# USB.net
KiCad netlist of a schematic drawn in Altium Designer
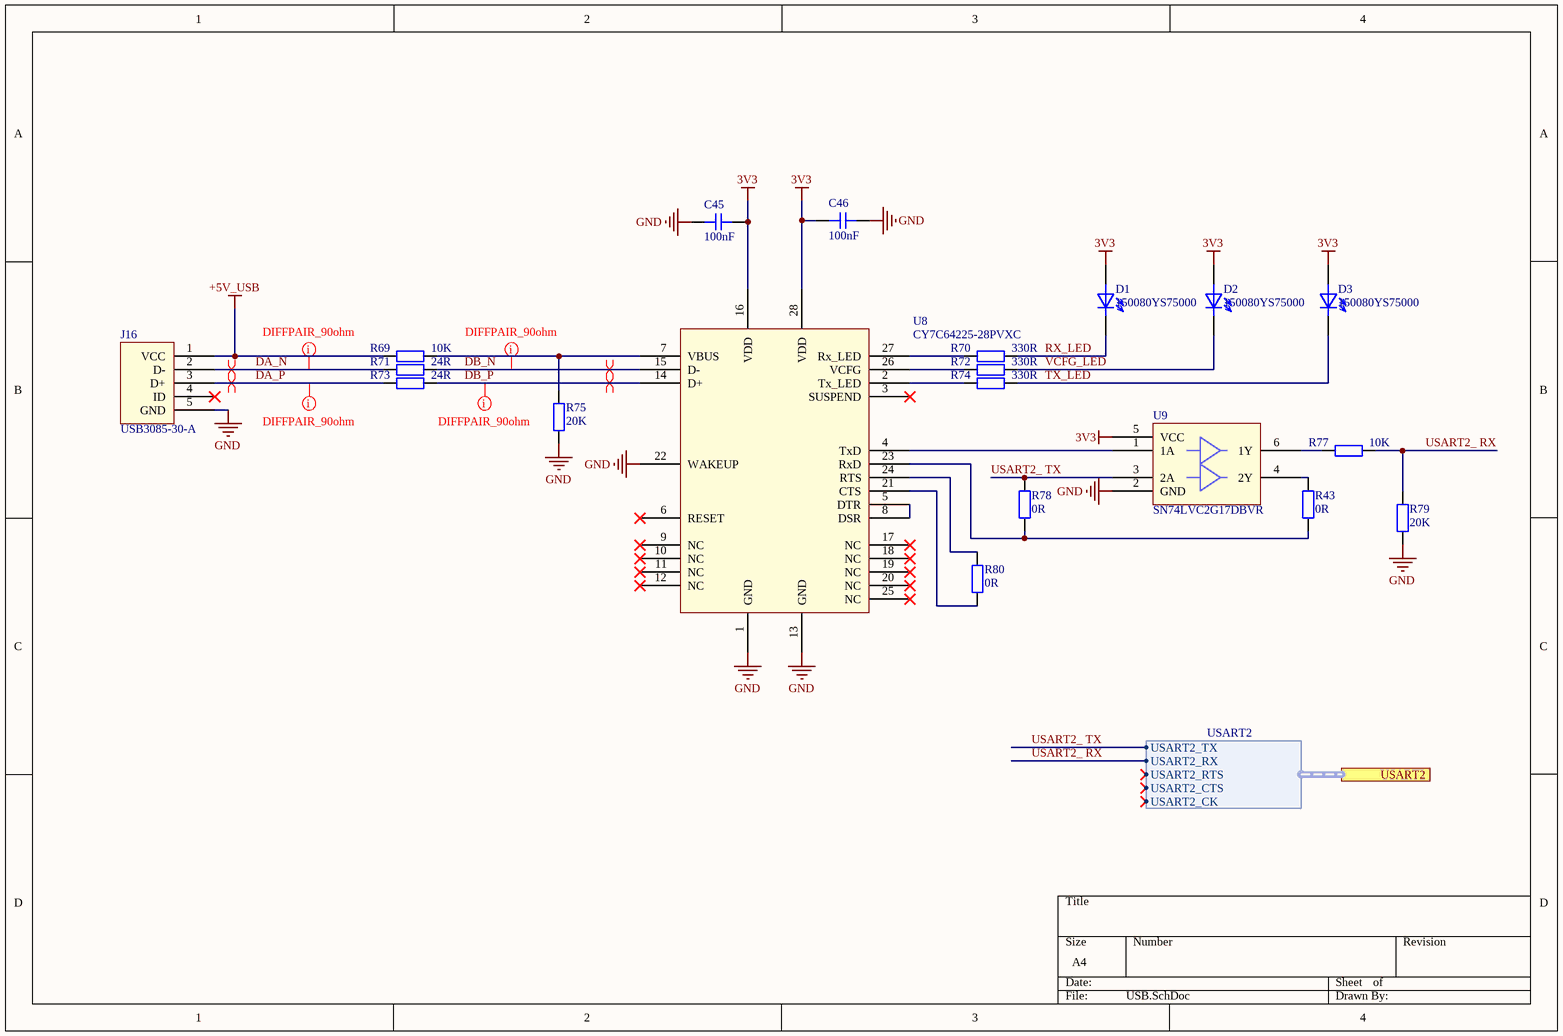
[diagram p0: USB.SchDoc]

(export (version "E")
  (design (tool "Eeschema 10.0.6"))
  (components
    (comp (ref "C45")
      (value "100nF")
      (footprint "Capacitor-0603")
      (fields (field (name "Comment") "C-100nF-0603"))
      (libsource (lib "Components") (part "C-100nF-0603"))
    )
    (comp (ref "C46")
      (value "100nF")
      (footprint "Capacitor-0603")
      (fields (field (name "Comment") "C-100nF-0603"))
      (libsource (lib "Components") (part "C-100nF-0603"))
    )
    (comp (ref "D1")
      (value "150080YS75000")
      (footprint "150080YS75000")
      (libsource (lib "Components") (part "150080YS75000"))
    )
    (comp (ref "D2")
      (value "150080YS75000")
      (footprint "150080YS75000")
      (libsource (lib "Components") (part "150080YS75000"))
    )
    (comp (ref "D3")
      (value "150080YS75000")
      (footprint "150080YS75000")
      (libsource (lib "Components") (part "150080YS75000"))
    )
    (comp (ref "J16")
      (value "USB3085-30-A")
      (footprint "USB3085-30-A")
      (libsource (lib "Components") (part "USB3085-30-A"))
    )
    (comp (ref "R43")
      (value "0R")
      (footprint "Resistor-0603")
      (fields (field (name "Comment") "R-0R-0603"))
      (libsource (lib "Components") (part "R-0R-0603"))
    )
    (comp (ref "R69")
      (value "10K")
      (footprint "Resistor-0603")
      (fields (field (name "Comment") "R-10K-0603"))
      (libsource (lib "Components") (part "R-10K-0603"))
    )
    (comp (ref "R70")
      (value "330R")
      (footprint "Resistor-0603")
      (fields (field (name "Comment") "R-330R-0603"))
      (libsource (lib "Components") (part "R-330R-0603"))
    )
    (comp (ref "R71")
      (value "24R")
      (footprint "Resistor-0603")
      (fields (field (name "Comment") "R-24R-0603"))
      (libsource (lib "Components") (part "R-24R-0603"))
    )
    (comp (ref "R72")
      (value "330R")
      (footprint "Resistor-0603")
      (fields (field (name "Comment") "R-330R-0603"))
      (libsource (lib "Components") (part "R-330R-0603"))
    )
    (comp (ref "R73")
      (value "24R")
      (footprint "Resistor-0603")
      (fields (field (name "Comment") "R-24R-0603"))
      (libsource (lib "Components") (part "R-24R-0603"))
    )
    (comp (ref "R74")
      (value "330R")
      (footprint "Resistor-0603")
      (fields (field (name "Comment") "R-330R-0603"))
      (libsource (lib "Components") (part "R-330R-0603"))
    )
    (comp (ref "R75")
      (value "20K")
      (footprint "Resistor-0603")
      (fields (field (name "Comment") "R-20K-0603"))
      (libsource (lib "Components") (part "R-20K-0603"))
    )
    (comp (ref "R77")
      (value "10K")
      (footprint "Resistor-0603")
      (fields (field (name "Comment") "R-10K-0603"))
      (libsource (lib "Components") (part "R-10K-0603"))
    )
    (comp (ref "R78")
      (value "0R")
      (footprint "Resistor-0603")
      (fields (field (name "Comment") "R-0R-0603"))
      (libsource (lib "Components") (part "R-0R-0603"))
    )
    (comp (ref "R79")
      (value "20K")
      (footprint "Resistor-0603")
      (fields (field (name "Comment") "R-20K-0603"))
      (libsource (lib "Components") (part "R-20K-0603"))
    )
    (comp (ref "R80")
      (value "0R")
      (footprint "Resistor-0603")
      (fields (field (name "Comment") "R-0R-0603"))
      (libsource (lib "Components") (part "R-0R-0603"))
    )
    (comp (ref "U8")
      (value "CY7C64225-28PVXC")
      (footprint "CY7C64225-28PVXC")
      (libsource (lib "Components") (part "CY7C64225-28PVXC"))
    )
    (comp (ref "U9")
      (value "SN74LVC2G17DBVR")
      (footprint "SN74LVC2G17DBVR")
      (libsource (lib "Components") (part "SN74LVC2G17DBVR"))
    )
  )
  (nets
    (net (code "2") (name "+5V_USB") (class "Default")
      (node (ref "J16") (pin "1") (pinfunction "VCC_1") (pintype "passive"))
      (node (ref "R69") (pin "1") (pinfunction "1_1") (pintype "passive"))
    )
    (net (code "3") (name "/DA_N") (class "Default")
      (node (ref "J16") (pin "2") (pinfunction "D-_2") (pintype "passive"))
      (node (ref "R71") (pin "1") (pinfunction "1_1") (pintype "passive"))
    )
    (net (code "4") (name "/DA_P") (class "Default")
      (node (ref "J16") (pin "3") (pinfunction "D+_3") (pintype "passive"))
      (node (ref "R73") (pin "1") (pinfunction "1_1") (pintype "passive"))
    )
    (net (code "5") (name "/DB_N") (class "Default")
      (node (ref "R71") (pin "2") (pinfunction "2_2") (pintype "passive"))
      (node (ref "U8") (pin "15") (pinfunction "D-_15") (pintype "passive"))
    )
    (net (code "6") (name "/DB_P") (class "Default")
      (node (ref "R73") (pin "2") (pinfunction "2_2") (pintype "passive"))
      (node (ref "U8") (pin "14") (pinfunction "D+_14") (pintype "passive"))
    )
    (net (code "7") (name "/RX_LED") (class "Default")
      (node (ref "D1") (pin "1") (pinfunction "1_1") (pintype "passive"))
      (node (ref "R70") (pin "2") (pinfunction "2_2") (pintype "passive"))
    )
    (net (code "8") (name "/TX_LED") (class "Default")
      (node (ref "D3") (pin "1") (pinfunction "1_1") (pintype "passive"))
      (node (ref "R74") (pin "2") (pinfunction "2_2") (pintype "passive"))
    )
    (net (code "9") (name "/USART2_ RX") (class "Default")
      (node (ref "R77") (pin "2") (pinfunction "2_2") (pintype "passive"))
      (node (ref "R79") (pin "2") (pinfunction "2_2") (pintype "passive"))
    )
    (net (code "10") (name "/USART2_ TX") (class "Default")
      (node (ref "R78") (pin "2") (pinfunction "2_2") (pintype "passive"))
      (node (ref "U9") (pin "3") (pinfunction "2A_3") (pintype "passive"))
    )
    (net (code "11") (name "/VCFG_LED") (class "Default")
      (node (ref "D2") (pin "1") (pinfunction "1_1") (pintype "passive"))
      (node (ref "R72") (pin "2") (pinfunction "2_2") (pintype "passive"))
    )
    (net (code "13") (name "3V3") (class "Default")
      (node (ref "C45") (pin "1") (pinfunction "1_1") (pintype "passive"))
      (node (ref "C46") (pin "1") (pinfunction "1_1") (pintype "passive"))
      (node (ref "D1") (pin "2") (pinfunction "2_2") (pintype "passive"))
      (node (ref "D2") (pin "2") (pinfunction "2_2") (pintype "passive"))
      (node (ref "D3") (pin "2") (pinfunction "2_2") (pintype "passive"))
      (node (ref "U8") (pin "16") (pinfunction "VDD_16") (pintype "passive"))
      (node (ref "U8") (pin "28") (pinfunction "VDD_28") (pintype "passive"))
      (node (ref "U9") (pin "5") (pinfunction "VCC_5") (pintype "passive"))
    )
    (net (code "14") (name "GND") (class "Default")
      (node (ref "C45") (pin "2") (pinfunction "2_2") (pintype "passive"))
      (node (ref "C46") (pin "2") (pinfunction "2_2") (pintype "passive"))
      (node (ref "J16") (pin "5") (pinfunction "GND_5") (pintype "passive"))
      (node (ref "R75") (pin "1") (pinfunction "1_1") (pintype "passive"))
      (node (ref "R79") (pin "1") (pinfunction "1_1") (pintype "passive"))
      (node (ref "U8") (pin "1") (pinfunction "GND_1") (pintype "passive"))
      (node (ref "U8") (pin "13") (pinfunction "GND_13") (pintype "passive"))
      (node (ref "U8") (pin "22") (pinfunction "WAKEUP_22") (pintype "passive"))
      (node (ref "U9") (pin "2") (pinfunction "GND_2") (pintype "passive"))
    )
    (net (code "15") (name "Net-(U8-CTS)") (class "Default")
      (node (ref "R80") (pin "1") (pinfunction "1_1") (pintype "passive"))
      (node (ref "U8") (pin "21") (pinfunction "CTS_21") (pintype "passive"))
    )
    (net (code "16") (name "Net-(U8-DSR)") (class "Default")
      (node (ref "U8") (pin "5") (pinfunction "DTR_5") (pintype "passive"))
      (node (ref "U8") (pin "8") (pinfunction "DSR_8") (pintype "passive"))
    )
    (net (code "17") (name "Net-(U8-RTS)") (class "Default")
      (node (ref "R80") (pin "2") (pinfunction "2_2") (pintype "passive"))
      (node (ref "U8") (pin "24") (pinfunction "RTS_24") (pintype "passive"))
    )
    (net (code "18") (name "Net-(U8-RxD)") (class "Default")
      (node (ref "R43") (pin "1") (pinfunction "1_1") (pintype "passive"))
      (node (ref "R78") (pin "1") (pinfunction "1_1") (pintype "passive"))
      (node (ref "U8") (pin "23") (pinfunction "RxD_23") (pintype "passive"))
    )
    (net (code "19") (name "Net-(U8-Rx_LED)") (class "Default")
      (node (ref "R70") (pin "1") (pinfunction "1_1") (pintype "passive"))
      (node (ref "U8") (pin "27") (pinfunction "Rx_LED_27") (pintype "passive"))
    )
    (net (code "20") (name "Net-(U8-TxD)") (class "Default")
      (node (ref "U8") (pin "4") (pinfunction "TxD_4") (pintype "passive"))
      (node (ref "U9") (pin "1") (pinfunction "1A_1") (pintype "passive"))
    )
    (net (code "21") (name "Net-(U8-Tx_LED)") (class "Default")
      (node (ref "R74") (pin "1") (pinfunction "1_1") (pintype "passive"))
      (node (ref "U8") (pin "2") (pinfunction "Tx_LED_2") (pintype "passive"))
    )
    (net (code "22") (name "Net-(U8-VBUS)") (class "Default")
      (node (ref "R69") (pin "2") (pinfunction "2_2") (pintype "passive"))
      (node (ref "R75") (pin "2") (pinfunction "2_2") (pintype "passive"))
      (node (ref "U8") (pin "7") (pinfunction "VBUS_7") (pintype "passive"))
    )
    (net (code "23") (name "Net-(U8-VCFG)") (class "Default")
      (node (ref "R72") (pin "1") (pinfunction "1_1") (pintype "passive"))
      (node (ref "U8") (pin "26") (pinfunction "VCFG_26") (pintype "passive"))
    )
    (net (code "24") (name "Net-(U9-1Y)") (class "Default")
      (node (ref "R77") (pin "1") (pinfunction "1_1") (pintype "passive"))
      (node (ref "U9") (pin "6") (pinfunction "1Y_6") (pintype "passive"))
    )
    (net (code "25") (name "Net-(U9-2Y)") (class "Default")
      (node (ref "R43") (pin "2") (pinfunction "2_2") (pintype "passive"))
      (node (ref "U9") (pin "4") (pinfunction "2Y_4") (pintype "passive"))
    )
    (net (code "26") (name "unconnected-(J16-ID-Pad4)") (class "Default")
      (node (ref "J16") (pin "4") (pinfunction "ID_4") (pintype "passive+no_connect"))
    )
    (net (code "27") (name "unconnected-(U8-NC-Pad9)") (class "Default")
      (node (ref "U8") (pin "9") (pinfunction "NC_9") (pintype "passive+no_connect"))
    )
    (net (code "28") (name "unconnected-(U8-NC-Pad10)") (class "Default")
      (node (ref "U8") (pin "10") (pinfunction "NC_10") (pintype "passive+no_connect"))
    )
    (net (code "29") (name "unconnected-(U8-NC-Pad11)") (class "Default")
      (node (ref "U8") (pin "11") (pinfunction "NC_11") (pintype "passive+no_connect"))
    )
    (net (code "30") (name "unconnected-(U8-NC-Pad12)") (class "Default")
      (node (ref "U8") (pin "12") (pinfunction "NC_12") (pintype "passive+no_connect"))
    )
    (net (code "31") (name "unconnected-(U8-NC-Pad17)") (class "Default")
      (node (ref "U8") (pin "17") (pinfunction "NC_17") (pintype "passive+no_connect"))
    )
    (net (code "32") (name "unconnected-(U8-NC-Pad18)") (class "Default")
      (node (ref "U8") (pin "18") (pinfunction "NC_18") (pintype "passive+no_connect"))
    )
    (net (code "33") (name "unconnected-(U8-NC-Pad19)") (class "Default")
      (node (ref "U8") (pin "19") (pinfunction "NC_19") (pintype "passive+no_connect"))
    )
    (net (code "34") (name "unconnected-(U8-NC-Pad20)") (class "Default")
      (node (ref "U8") (pin "20") (pinfunction "NC_20") (pintype "passive+no_connect"))
    )
    (net (code "35") (name "unconnected-(U8-NC-Pad25)") (class "Default")
      (node (ref "U8") (pin "25") (pinfunction "NC_25") (pintype "passive+no_connect"))
    )
    (net (code "36") (name "unconnected-(U8-RESET-Pad6)") (class "Default")
      (node (ref "U8") (pin "6") (pinfunction "RESET_6") (pintype "passive+no_connect"))
    )
    (net (code "37") (name "unconnected-(U8-SUSPEND-Pad3)") (class "Default")
      (node (ref "U8") (pin "3") (pinfunction "SUSPEND_3") (pintype "passive+no_connect"))
    )
  )
)
